# CanBus-Y.net
KiCad netlist of a schematic drawn in EAGLE
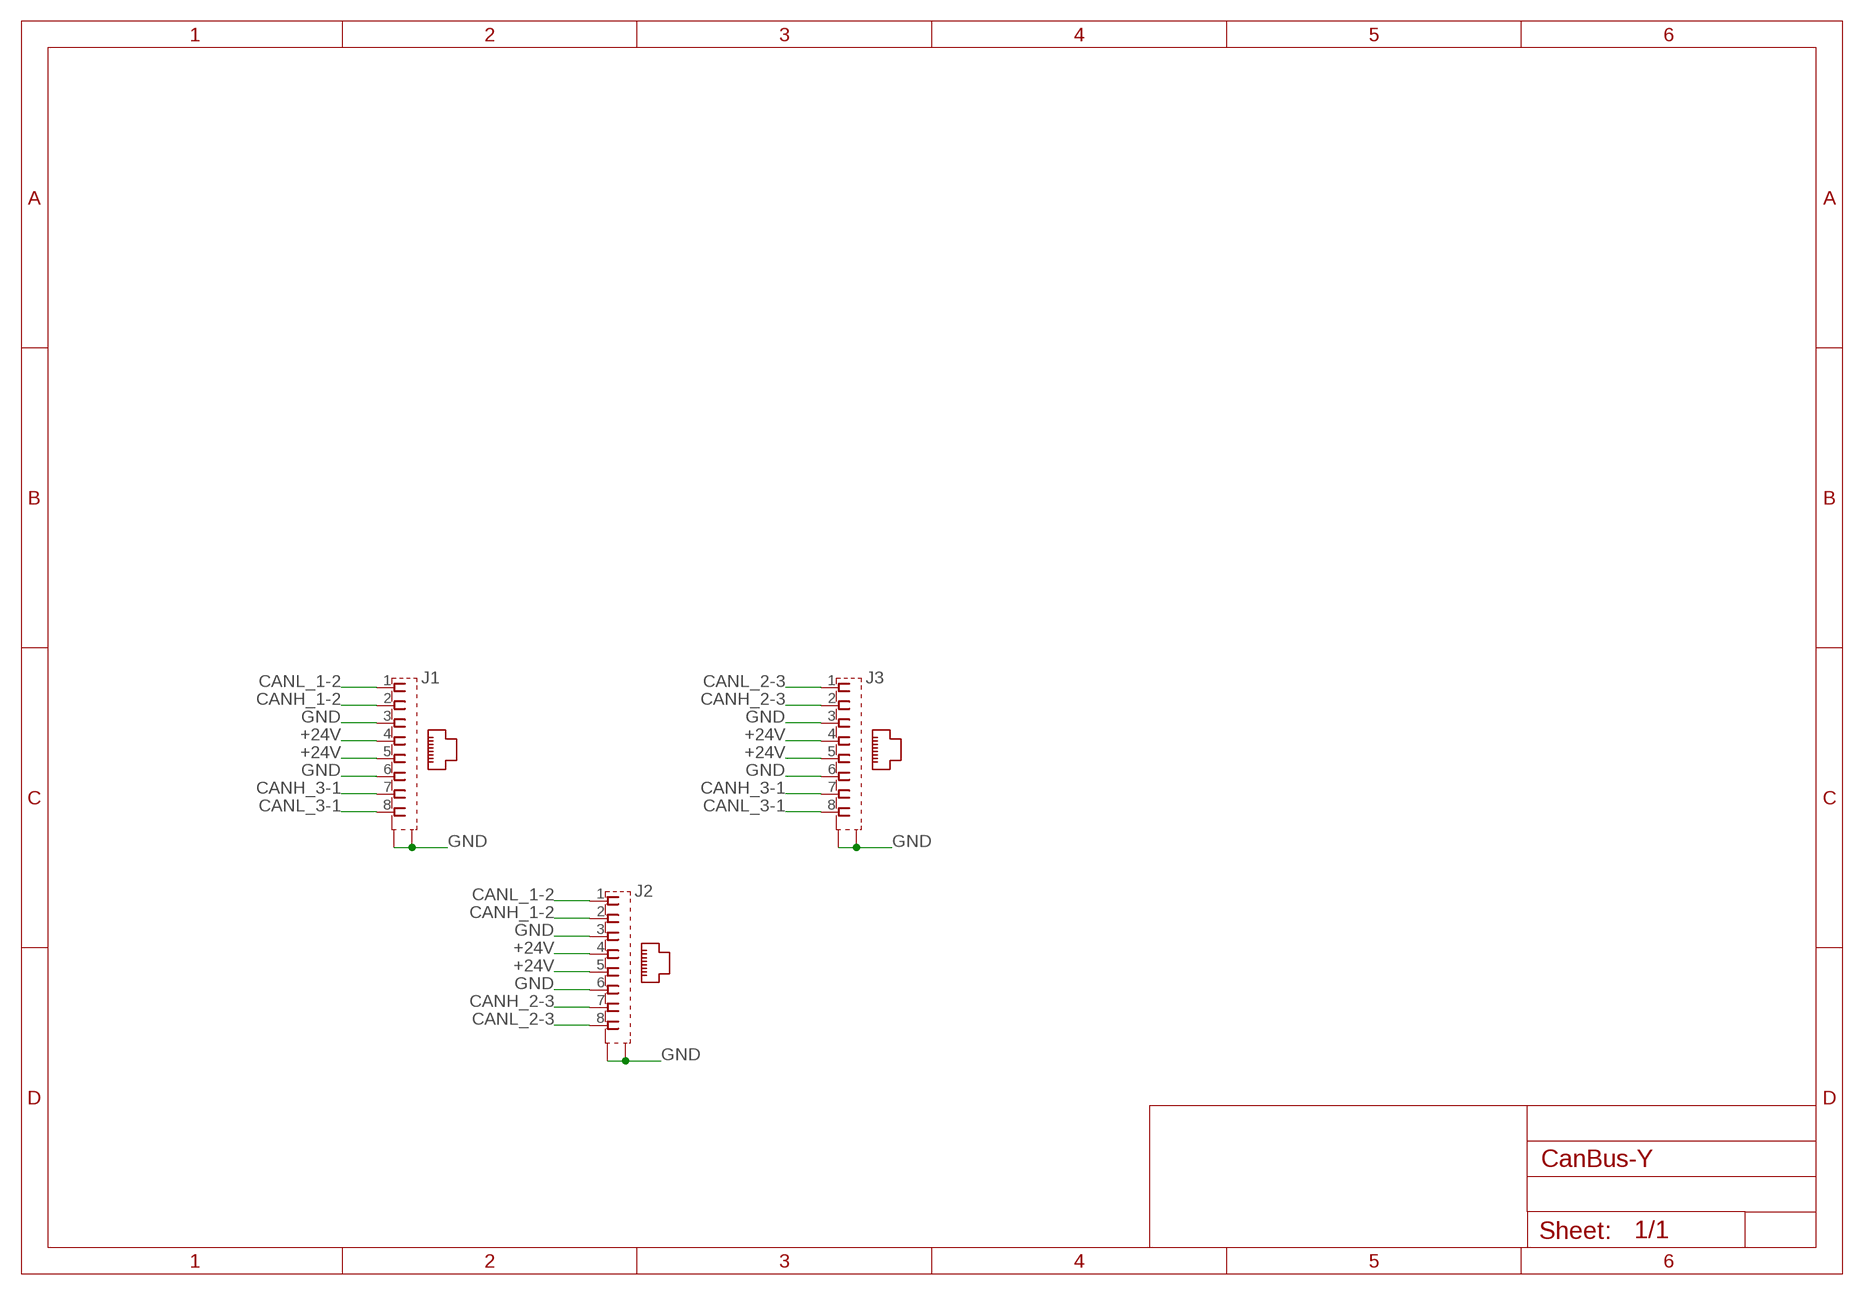
[diagram p0: schematic, sheet 1]

(export (version "E")
  (design (tool "Eeschema 10.0.6"))
  (components
    (comp (ref "J1")
      (value "555141-1")
      (footprint "eagle-import:MEBP_8-8G")
      (libsource (lib "eagle-import") (part "555141-1"))
    )
    (comp (ref "J2")
      (value "555141-1")
      (footprint "eagle-import:MEBP_8-8G")
      (libsource (lib "eagle-import") (part "555141-1"))
    )
    (comp (ref "J3")
      (value "555141-1")
      (footprint "eagle-import:MEBP_8-8G")
      (libsource (lib "eagle-import") (part "555141-1"))
    )
  )
  (nets
    (net (code "1") (name "/+24V") (class "Default")
      (node (ref "J1") (pin "4") (pinfunction "4_4") (pintype "passive"))
      (node (ref "J1") (pin "5") (pinfunction "5_5") (pintype "passive"))
      (node (ref "J2") (pin "4") (pinfunction "4_4") (pintype "passive"))
      (node (ref "J2") (pin "5") (pinfunction "5_5") (pintype "passive"))
      (node (ref "J3") (pin "4") (pinfunction "4_4") (pintype "passive"))
      (node (ref "J3") (pin "5") (pinfunction "5_5") (pintype "passive"))
    )
    (net (code "2") (name "/CANH_1-2") (class "Default")
      (node (ref "J1") (pin "2") (pinfunction "2_2") (pintype "passive"))
      (node (ref "J2") (pin "2") (pinfunction "2_2") (pintype "passive"))
    )
    (net (code "3") (name "/CANH_2-3") (class "Default")
      (node (ref "J2") (pin "7") (pinfunction "7_7") (pintype "passive"))
      (node (ref "J3") (pin "2") (pinfunction "2_2") (pintype "passive"))
    )
    (net (code "4") (name "/CANH_3-1") (class "Default")
      (node (ref "J1") (pin "7") (pinfunction "7_7") (pintype "passive"))
      (node (ref "J3") (pin "7") (pinfunction "7_7") (pintype "passive"))
    )
    (net (code "5") (name "/CANL_1-2") (class "Default")
      (node (ref "J1") (pin "1") (pinfunction "1_1") (pintype "passive"))
      (node (ref "J2") (pin "1") (pinfunction "1_1") (pintype "passive"))
    )
    (net (code "6") (name "/CANL_2-3") (class "Default")
      (node (ref "J2") (pin "8") (pinfunction "8_8") (pintype "passive"))
      (node (ref "J3") (pin "1") (pinfunction "1_1") (pintype "passive"))
    )
    (net (code "7") (name "/CANL_3-1") (class "Default")
      (node (ref "J1") (pin "8") (pinfunction "8_8") (pintype "passive"))
      (node (ref "J3") (pin "8") (pinfunction "8_8") (pintype "passive"))
    )
    (net (code "8") (name "/GND") (class "Default")
      (node (ref "J1") (pin "3") (pinfunction "3_3") (pintype "passive"))
      (node (ref "J1") (pin "6") (pinfunction "6_6") (pintype "passive"))
      (node (ref "J1") (pin "G1") (pinfunction "S1_G1") (pintype "passive"))
      (node (ref "J1") (pin "G2") (pinfunction "S2_G2") (pintype "passive"))
      (node (ref "J2") (pin "3") (pinfunction "3_3") (pintype "passive"))
      (node (ref "J2") (pin "6") (pinfunction "6_6") (pintype "passive"))
      (node (ref "J2") (pin "G1") (pinfunction "S1_G1") (pintype "passive"))
      (node (ref "J2") (pin "G2") (pinfunction "S2_G2") (pintype "passive"))
      (node (ref "J3") (pin "3") (pinfunction "3_3") (pintype "passive"))
      (node (ref "J3") (pin "6") (pinfunction "6_6") (pintype "passive"))
      (node (ref "J3") (pin "G1") (pinfunction "S1_G1") (pintype "passive"))
      (node (ref "J3") (pin "G2") (pinfunction "S2_G2") (pintype "passive"))
    )
  )
)
